# SCH_SCHEMA-LED-3_0_2025-04-29.net
KiCad netlist of a schematic drawn in EasyEDA
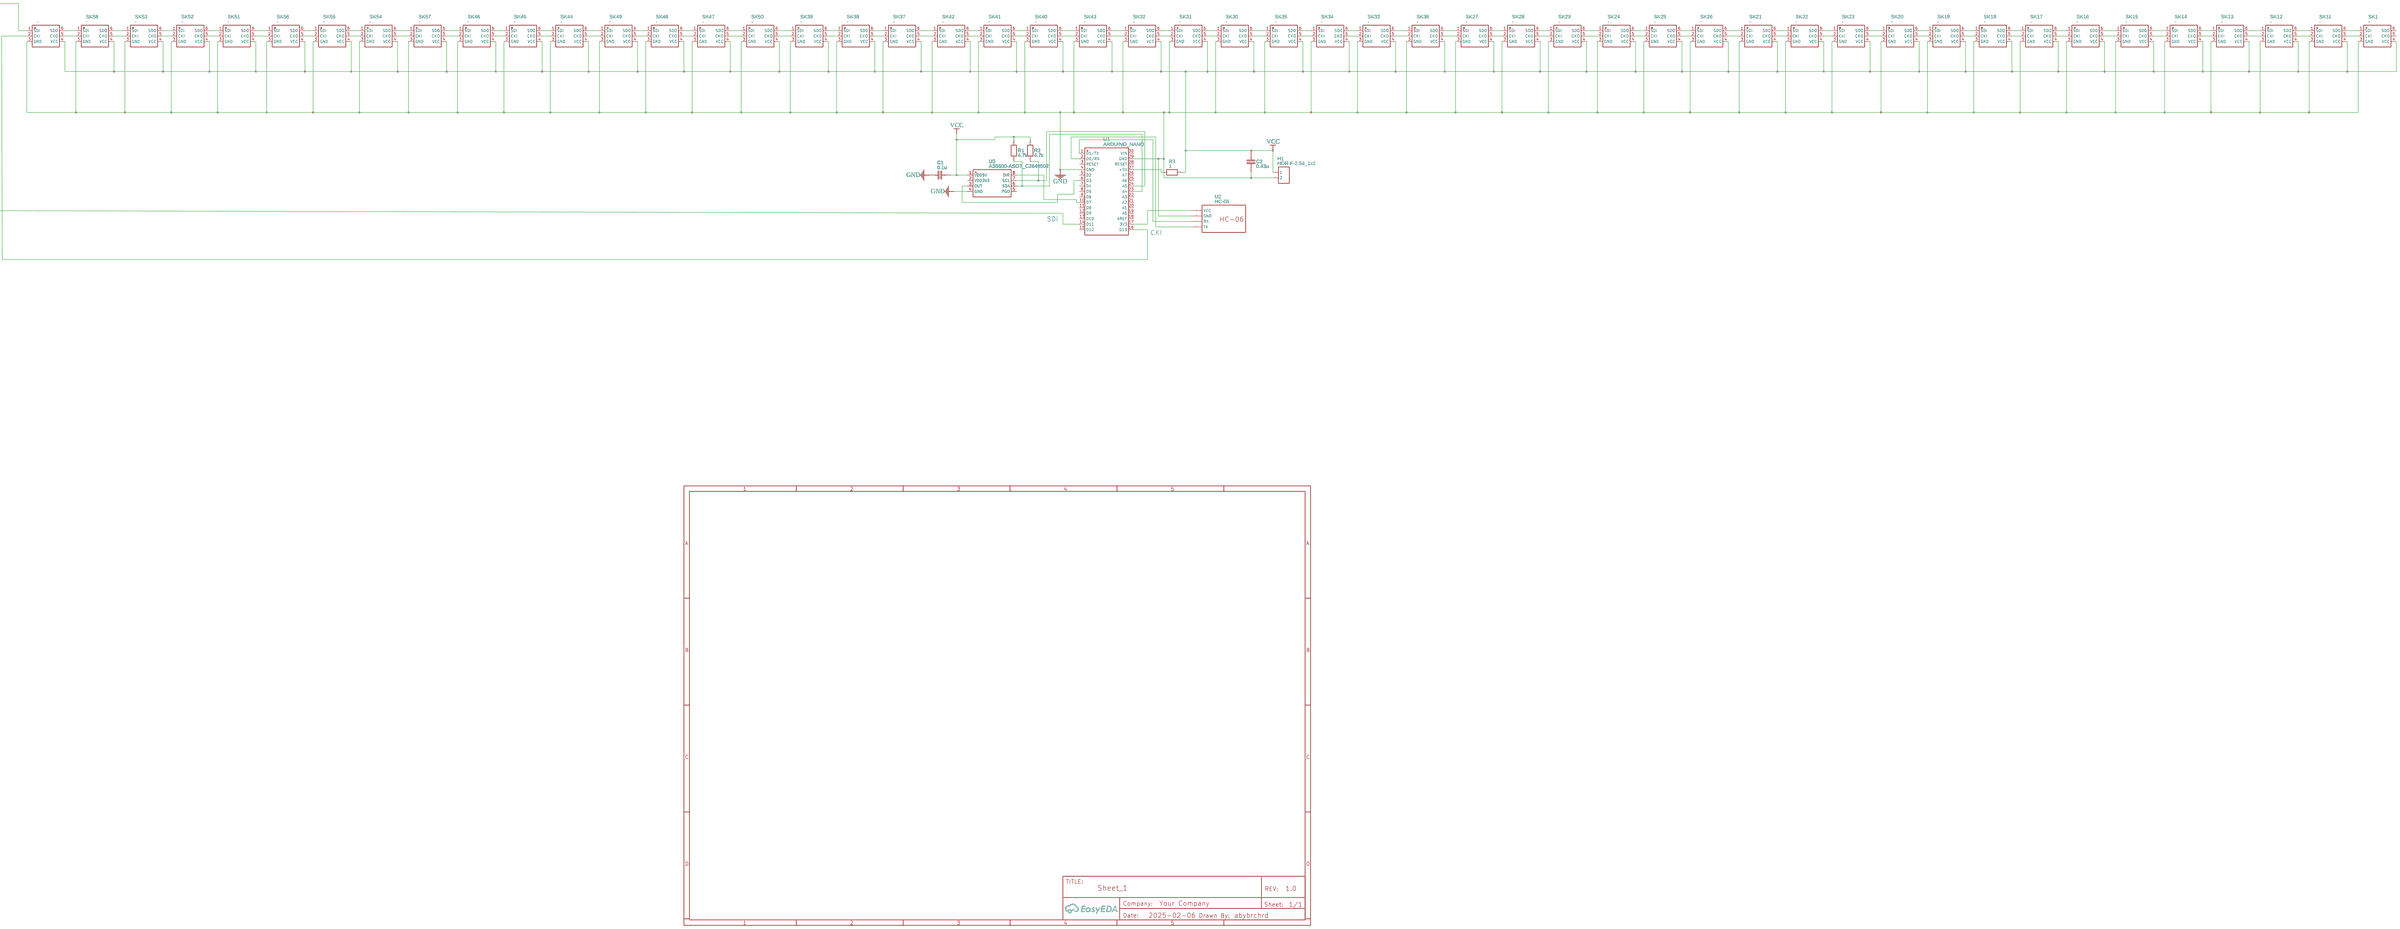
[diagram p0: schematic sheet]

(export (version "E")
  (design (tool "Eeschema 10.0.6"))
  (components
    (comp (ref "C1") (value "0.1u") (libsource (lib "") (part "C_0603_EU")))
    (comp (ref "C2") (value "0.43u") (libsource (lib "") (part "C_1206_EU")))
    (comp (ref "H1") (value "HDR-F-2.54_1x2") (libsource (lib "") (part "HDR-F-2.54_1x2")))
    (comp (ref "R1") (value "4.7k") (libsource (lib "") (part "R_0603_EU")))
    (comp (ref "R2") (value "4.7k") (libsource (lib "") (part "R_0603_EU")))
    (comp (ref "R3") (value "1") (libsource (lib "") (part "R_0603_EU_1")))
    (comp (ref "SK1")
      (value "-")
      (fields (field (name "Manufacturer Part") "SK9822") (field (name "Manufacturer") "欧思科光电"))
      (libsource (lib "") (part "SK9822"))
    )
    (comp (ref "SK11")
      (value "-")
      (fields (field (name "Manufacturer Part") "SK9822") (field (name "Manufacturer") "欧思科光电"))
      (libsource (lib "") (part "SK9822"))
    )
    (comp (ref "SK12")
      (value "-")
      (fields (field (name "Manufacturer Part") "SK9822") (field (name "Manufacturer") "欧思科光电"))
      (libsource (lib "") (part "SK9822"))
    )
    (comp (ref "SK13")
      (value "-")
      (fields (field (name "Manufacturer Part") "SK9822") (field (name "Manufacturer") "欧思科光电"))
      (libsource (lib "") (part "SK9822"))
    )
    (comp (ref "SK14")
      (value "-")
      (fields (field (name "Manufacturer Part") "SK9822") (field (name "Manufacturer") "欧思科光电"))
      (libsource (lib "") (part "SK9822"))
    )
    (comp (ref "SK15")
      (value "-")
      (fields (field (name "Manufacturer Part") "SK9822") (field (name "Manufacturer") "欧思科光电"))
      (libsource (lib "") (part "SK9822"))
    )
    (comp (ref "SK16")
      (value "-")
      (fields (field (name "Manufacturer Part") "SK9822") (field (name "Manufacturer") "欧思科光电"))
      (libsource (lib "") (part "SK9822"))
    )
    (comp (ref "SK17")
      (value "-")
      (fields (field (name "Manufacturer Part") "SK9822") (field (name "Manufacturer") "欧思科光电"))
      (libsource (lib "") (part "SK9822"))
    )
    (comp (ref "SK18")
      (value "-")
      (fields (field (name "Manufacturer Part") "SK9822") (field (name "Manufacturer") "欧思科光电"))
      (libsource (lib "") (part "SK9822"))
    )
    (comp (ref "SK19")
      (value "-")
      (fields (field (name "Manufacturer Part") "SK9822") (field (name "Manufacturer") "欧思科光电"))
      (libsource (lib "") (part "SK9822"))
    )
    (comp (ref "SK20")
      (value "-")
      (fields (field (name "Manufacturer Part") "SK9822") (field (name "Manufacturer") "欧思科光电"))
      (libsource (lib "") (part "SK9822"))
    )
    (comp (ref "SK21")
      (value "-")
      (fields (field (name "Manufacturer Part") "SK9822") (field (name "Manufacturer") "欧思科光电"))
      (libsource (lib "") (part "SK9822"))
    )
    (comp (ref "SK22")
      (value "-")
      (fields (field (name "Manufacturer Part") "SK9822") (field (name "Manufacturer") "欧思科光电"))
      (libsource (lib "") (part "SK9822"))
    )
    (comp (ref "SK23")
      (value "-")
      (fields (field (name "Manufacturer Part") "SK9822") (field (name "Manufacturer") "欧思科光电"))
      (libsource (lib "") (part "SK9822"))
    )
    (comp (ref "SK24")
      (value "-")
      (fields (field (name "Manufacturer Part") "SK9822") (field (name "Manufacturer") "欧思科光电"))
      (libsource (lib "") (part "SK9822"))
    )
    (comp (ref "SK25")
      (value "-")
      (fields (field (name "Manufacturer Part") "SK9822") (field (name "Manufacturer") "欧思科光电"))
      (libsource (lib "") (part "SK9822"))
    )
    (comp (ref "SK26")
      (value "-")
      (fields (field (name "Manufacturer Part") "SK9822") (field (name "Manufacturer") "欧思科光电"))
      (libsource (lib "") (part "SK9822"))
    )
    (comp (ref "SK27")
      (value "-")
      (fields (field (name "Manufacturer Part") "SK9822") (field (name "Manufacturer") "欧思科光电"))
      (libsource (lib "") (part "SK9822"))
    )
    (comp (ref "SK28")
      (value "-")
      (fields (field (name "Manufacturer Part") "SK9822") (field (name "Manufacturer") "欧思科光电"))
      (libsource (lib "") (part "SK9822"))
    )
    (comp (ref "SK29")
      (value "-")
      (fields (field (name "Manufacturer Part") "SK9822") (field (name "Manufacturer") "欧思科光电"))
      (libsource (lib "") (part "SK9822"))
    )
    (comp (ref "SK30")
      (value "-")
      (fields (field (name "Manufacturer Part") "SK9822") (field (name "Manufacturer") "欧思科光电"))
      (libsource (lib "") (part "SK9822"))
    )
    (comp (ref "SK31")
      (value "-")
      (fields (field (name "Manufacturer Part") "SK9822") (field (name "Manufacturer") "欧思科光电"))
      (libsource (lib "") (part "SK9822"))
    )
    (comp (ref "SK32")
      (value "-")
      (fields (field (name "Manufacturer Part") "SK9822") (field (name "Manufacturer") "欧思科光电"))
      (libsource (lib "") (part "SK9822"))
    )
    (comp (ref "SK33")
      (value "-")
      (fields (field (name "Manufacturer Part") "SK9822") (field (name "Manufacturer") "欧思科光电"))
      (libsource (lib "") (part "SK9822"))
    )
    (comp (ref "SK34")
      (value "-")
      (fields (field (name "Manufacturer Part") "SK9822") (field (name "Manufacturer") "欧思科光电"))
      (libsource (lib "") (part "SK9822"))
    )
    (comp (ref "SK35")
      (value "-")
      (fields (field (name "Manufacturer Part") "SK9822") (field (name "Manufacturer") "欧思科光电"))
      (libsource (lib "") (part "SK9822"))
    )
    (comp (ref "SK36")
      (value "-")
      (fields (field (name "Manufacturer Part") "SK9822") (field (name "Manufacturer") "欧思科光电"))
      (libsource (lib "") (part "SK9822"))
    )
    (comp (ref "SK37")
      (value "-")
      (fields (field (name "Manufacturer Part") "SK9822") (field (name "Manufacturer") "欧思科光电"))
      (libsource (lib "") (part "SK9822"))
    )
    (comp (ref "SK38")
      (value "-")
      (fields (field (name "Manufacturer Part") "SK9822") (field (name "Manufacturer") "欧思科光电"))
      (libsource (lib "") (part "SK9822"))
    )
    (comp (ref "SK39")
      (value "-")
      (fields (field (name "Manufacturer Part") "SK9822") (field (name "Manufacturer") "欧思科光电"))
      (libsource (lib "") (part "SK9822"))
    )
    (comp (ref "SK40")
      (value "-")
      (fields (field (name "Manufacturer Part") "SK9822") (field (name "Manufacturer") "欧思科光电"))
      (libsource (lib "") (part "SK9822"))
    )
    (comp (ref "SK41")
      (value "-")
      (fields (field (name "Manufacturer Part") "SK9822") (field (name "Manufacturer") "欧思科光电"))
      (libsource (lib "") (part "SK9822"))
    )
    (comp (ref "SK42")
      (value "-")
      (fields (field (name "Manufacturer Part") "SK9822") (field (name "Manufacturer") "欧思科光电"))
      (libsource (lib "") (part "SK9822"))
    )
    (comp (ref "SK43")
      (value "-")
      (fields (field (name "Manufacturer Part") "SK9822") (field (name "Manufacturer") "欧思科光电"))
      (libsource (lib "") (part "SK9822"))
    )
    (comp (ref "SK44")
      (value "-")
      (fields (field (name "Manufacturer Part") "SK9822") (field (name "Manufacturer") "欧思科光电"))
      (libsource (lib "") (part "SK9822"))
    )
    (comp (ref "SK45")
      (value "-")
      (fields (field (name "Manufacturer Part") "SK9822") (field (name "Manufacturer") "欧思科光电"))
      (libsource (lib "") (part "SK9822"))
    )
    (comp (ref "SK46")
      (value "-")
      (fields (field (name "Manufacturer Part") "SK9822") (field (name "Manufacturer") "欧思科光电"))
      (libsource (lib "") (part "SK9822"))
    )
    (comp (ref "SK47")
      (value "-")
      (fields (field (name "Manufacturer Part") "SK9822") (field (name "Manufacturer") "欧思科光电"))
      (libsource (lib "") (part "SK9822"))
    )
    (comp (ref "SK48")
      (value "-")
      (fields (field (name "Manufacturer Part") "SK9822") (field (name "Manufacturer") "欧思科光电"))
      (libsource (lib "") (part "SK9822"))
    )
    (comp (ref "SK49")
      (value "-")
      (fields (field (name "Manufacturer Part") "SK9822") (field (name "Manufacturer") "欧思科光电"))
      (libsource (lib "") (part "SK9822"))
    )
    (comp (ref "SK50")
      (value "-")
      (fields (field (name "Manufacturer Part") "SK9822") (field (name "Manufacturer") "欧思科光电"))
      (libsource (lib "") (part "SK9822"))
    )
    (comp (ref "SK51")
      (value "-")
      (fields (field (name "Manufacturer Part") "SK9822") (field (name "Manufacturer") "欧思科光电"))
      (libsource (lib "") (part "SK9822"))
    )
    (comp (ref "SK52")
      (value "-")
      (fields (field (name "Manufacturer Part") "SK9822") (field (name "Manufacturer") "欧思科光电"))
      (libsource (lib "") (part "SK9822"))
    )
    (comp (ref "SK53")
      (value "-")
      (fields (field (name "Manufacturer Part") "SK9822") (field (name "Manufacturer") "欧思科光电"))
      (libsource (lib "") (part "SK9822"))
    )
    (comp (ref "SK54")
      (value "-")
      (fields (field (name "Manufacturer Part") "SK9822") (field (name "Manufacturer") "欧思科光电"))
      (libsource (lib "") (part "SK9822"))
    )
    (comp (ref "SK55")
      (value "-")
      (fields (field (name "Manufacturer Part") "SK9822") (field (name "Manufacturer") "欧思科光电"))
      (libsource (lib "") (part "SK9822"))
    )
    (comp (ref "SK56")
      (value "-")
      (fields (field (name "Manufacturer Part") "SK9822") (field (name "Manufacturer") "欧思科光电"))
      (libsource (lib "") (part "SK9822"))
    )
    (comp (ref "SK57")
      (value "-")
      (fields (field (name "Manufacturer Part") "SK9822") (field (name "Manufacturer") "欧思科光电"))
      (libsource (lib "") (part "SK9822"))
    )
    (comp (ref "SK58")
      (value "-")
      (fields (field (name "Manufacturer Part") "SK9822") (field (name "Manufacturer") "欧思科光电"))
      (libsource (lib "") (part "SK9822"))
    )
    (comp (ref "SK59")
      (value "-")
      (fields (field (name "Manufacturer Part") "SK9822") (field (name "Manufacturer") "欧思科光电"))
      (libsource (lib "") (part "SK9822"))
    )
    (comp (ref "U1") (value "ARDUINO_NANO") (libsource (lib "") (part "ARDUINO_NANO")))
    (comp (ref "U2") (value "HC-06") (libsource (lib "") (part "HC-06")))
    (comp (ref "U3")
      (value "AS5600-ASOT_C2649502")
      (fields (field (name "Manufacturer Part") "AS5600-ASOT") (field (name "Manufacturer") "ams(艾迈斯半导体)"))
      (libsource (lib "") (part "AS5600-ASOT_C2649502"))
    )
  )
  (nets
    (net (code "1") (name "GND") (class "Default")
      (node (ref "C1") (pin "1") (pinfunction "1_1") (pintype "unspecified"))
      (node (ref "C2") (pin "1") (pinfunction "1_1") (pintype "unspecified"))
      (node (ref "H1") (pin "2") (pinfunction "2_2") (pintype "input"))
      (node (ref "SK1") (pin "3") (pinfunction "GND_3") (pintype "unspecified"))
      (node (ref "SK11") (pin "3") (pinfunction "GND_3") (pintype "unspecified"))
      (node (ref "SK12") (pin "3") (pinfunction "GND_3") (pintype "unspecified"))
      (node (ref "SK13") (pin "3") (pinfunction "GND_3") (pintype "unspecified"))
      (node (ref "SK14") (pin "3") (pinfunction "GND_3") (pintype "unspecified"))
      (node (ref "SK15") (pin "3") (pinfunction "GND_3") (pintype "unspecified"))
      (node (ref "SK16") (pin "3") (pinfunction "GND_3") (pintype "unspecified"))
      (node (ref "SK17") (pin "3") (pinfunction "GND_3") (pintype "unspecified"))
      (node (ref "SK18") (pin "3") (pinfunction "GND_3") (pintype "unspecified"))
      (node (ref "SK19") (pin "3") (pinfunction "GND_3") (pintype "unspecified"))
      (node (ref "SK20") (pin "3") (pinfunction "GND_3") (pintype "unspecified"))
      (node (ref "SK21") (pin "3") (pinfunction "GND_3") (pintype "unspecified"))
      (node (ref "SK22") (pin "3") (pinfunction "GND_3") (pintype "unspecified"))
      (node (ref "SK23") (pin "3") (pinfunction "GND_3") (pintype "unspecified"))
      (node (ref "SK24") (pin "3") (pinfunction "GND_3") (pintype "unspecified"))
      (node (ref "SK25") (pin "3") (pinfunction "GND_3") (pintype "unspecified"))
      (node (ref "SK26") (pin "3") (pinfunction "GND_3") (pintype "unspecified"))
      (node (ref "SK27") (pin "3") (pinfunction "GND_3") (pintype "unspecified"))
      (node (ref "SK28") (pin "3") (pinfunction "GND_3") (pintype "unspecified"))
      (node (ref "SK29") (pin "3") (pinfunction "GND_3") (pintype "unspecified"))
      (node (ref "SK30") (pin "3") (pinfunction "GND_3") (pintype "unspecified"))
      (node (ref "SK31") (pin "3") (pinfunction "GND_3") (pintype "unspecified"))
      (node (ref "SK32") (pin "3") (pinfunction "GND_3") (pintype "unspecified"))
      (node (ref "SK33") (pin "3") (pinfunction "GND_3") (pintype "unspecified"))
      (node (ref "SK34") (pin "3") (pinfunction "GND_3") (pintype "unspecified"))
      (node (ref "SK35") (pin "3") (pinfunction "GND_3") (pintype "unspecified"))
      (node (ref "SK36") (pin "3") (pinfunction "GND_3") (pintype "unspecified"))
      (node (ref "SK37") (pin "3") (pinfunction "GND_3") (pintype "unspecified"))
      (node (ref "SK38") (pin "3") (pinfunction "GND_3") (pintype "unspecified"))
      (node (ref "SK39") (pin "3") (pinfunction "GND_3") (pintype "unspecified"))
      (node (ref "SK40") (pin "3") (pinfunction "GND_3") (pintype "unspecified"))
      (node (ref "SK41") (pin "3") (pinfunction "GND_3") (pintype "unspecified"))
      (node (ref "SK42") (pin "3") (pinfunction "GND_3") (pintype "unspecified"))
      (node (ref "SK43") (pin "3") (pinfunction "GND_3") (pintype "unspecified"))
      (node (ref "SK44") (pin "3") (pinfunction "GND_3") (pintype "unspecified"))
      (node (ref "SK45") (pin "3") (pinfunction "GND_3") (pintype "unspecified"))
      (node (ref "SK46") (pin "3") (pinfunction "GND_3") (pintype "unspecified"))
      (node (ref "SK47") (pin "3") (pinfunction "GND_3") (pintype "unspecified"))
      (node (ref "SK48") (pin "3") (pinfunction "GND_3") (pintype "unspecified"))
      (node (ref "SK49") (pin "3") (pinfunction "GND_3") (pintype "unspecified"))
      (node (ref "SK50") (pin "3") (pinfunction "GND_3") (pintype "unspecified"))
      (node (ref "SK51") (pin "3") (pinfunction "GND_3") (pintype "unspecified"))
      (node (ref "SK52") (pin "3") (pinfunction "GND_3") (pintype "unspecified"))
      (node (ref "SK53") (pin "3") (pinfunction "GND_3") (pintype "unspecified"))
      (node (ref "SK54") (pin "3") (pinfunction "GND_3") (pintype "unspecified"))
      (node (ref "SK55") (pin "3") (pinfunction "GND_3") (pintype "unspecified"))
      (node (ref "SK56") (pin "3") (pinfunction "GND_3") (pintype "unspecified"))
      (node (ref "SK57") (pin "3") (pinfunction "GND_3") (pintype "unspecified"))
      (node (ref "SK58") (pin "3") (pinfunction "GND_3") (pintype "unspecified"))
      (node (ref "SK59") (pin "3") (pinfunction "GND_3") (pintype "unspecified"))
      (node (ref "U1") (pin "29") (pinfunction "GND_29") (pintype "unspecified"))
      (node (ref "U1") (pin "4") (pinfunction "GND_4") (pintype "unspecified"))
      (node (ref "U2") (pin "3") (pinfunction "GND_3") (pintype "unspecified"))
      (node (ref "U3") (pin "4") (pinfunction "GND_4") (pintype "unspecified"))
    )
    (net (code "2") (name "Net-(SK1-CKI)") (class "Default")
      (node (ref "SK1") (pin "2") (pinfunction "CKI_2") (pintype "unspecified"))
      (node (ref "SK11") (pin "5") (pinfunction "CKO_5") (pintype "unspecified"))
    )
    (net (code "3") (name "Net-(SK1-SDI)") (class "Default")
      (node (ref "SK1") (pin "1") (pinfunction "SDI_1") (pintype "unspecified"))
      (node (ref "SK11") (pin "6") (pinfunction "SDO_6") (pintype "unspecified"))
    )
    (net (code "4") (name "Net-(SK11-CKI)") (class "Default")
      (node (ref "SK11") (pin "2") (pinfunction "CKI_2") (pintype "unspecified"))
      (node (ref "SK12") (pin "5") (pinfunction "CKO_5") (pintype "unspecified"))
    )
    (net (code "5") (name "Net-(SK11-SDI)") (class "Default")
      (node (ref "SK11") (pin "1") (pinfunction "SDI_1") (pintype "unspecified"))
      (node (ref "SK12") (pin "6") (pinfunction "SDO_6") (pintype "unspecified"))
    )
    (net (code "6") (name "Net-(SK12-CKI)") (class "Default")
      (node (ref "SK12") (pin "2") (pinfunction "CKI_2") (pintype "unspecified"))
      (node (ref "SK13") (pin "5") (pinfunction "CKO_5") (pintype "unspecified"))
    )
    (net (code "7") (name "Net-(SK12-SDI)") (class "Default")
      (node (ref "SK12") (pin "1") (pinfunction "SDI_1") (pintype "unspecified"))
      (node (ref "SK13") (pin "6") (pinfunction "SDO_6") (pintype "unspecified"))
    )
    (net (code "8") (name "Net-(SK13-CKI)") (class "Default")
      (node (ref "SK13") (pin "2") (pinfunction "CKI_2") (pintype "unspecified"))
      (node (ref "SK14") (pin "5") (pinfunction "CKO_5") (pintype "unspecified"))
    )
    (net (code "9") (name "Net-(SK13-SDI)") (class "Default")
      (node (ref "SK13") (pin "1") (pinfunction "SDI_1") (pintype "unspecified"))
      (node (ref "SK14") (pin "6") (pinfunction "SDO_6") (pintype "unspecified"))
    )
    (net (code "10") (name "Net-(SK14-CKI)") (class "Default")
      (node (ref "SK14") (pin "2") (pinfunction "CKI_2") (pintype "unspecified"))
      (node (ref "SK15") (pin "5") (pinfunction "CKO_5") (pintype "unspecified"))
    )
    (net (code "11") (name "Net-(SK14-SDI)") (class "Default")
      (node (ref "SK14") (pin "1") (pinfunction "SDI_1") (pintype "unspecified"))
      (node (ref "SK15") (pin "6") (pinfunction "SDO_6") (pintype "unspecified"))
    )
    (net (code "12") (name "Net-(SK15-CKI)") (class "Default")
      (node (ref "SK15") (pin "2") (pinfunction "CKI_2") (pintype "unspecified"))
      (node (ref "SK16") (pin "5") (pinfunction "CKO_5") (pintype "unspecified"))
    )
    (net (code "13") (name "Net-(SK15-SDI)") (class "Default")
      (node (ref "SK15") (pin "1") (pinfunction "SDI_1") (pintype "unspecified"))
      (node (ref "SK16") (pin "6") (pinfunction "SDO_6") (pintype "unspecified"))
    )
    (net (code "14") (name "Net-(SK16-CKI)") (class "Default")
      (node (ref "SK16") (pin "2") (pinfunction "CKI_2") (pintype "unspecified"))
      (node (ref "SK17") (pin "5") (pinfunction "CKO_5") (pintype "unspecified"))
    )
    (net (code "15") (name "Net-(SK16-SDI)") (class "Default")
      (node (ref "SK16") (pin "1") (pinfunction "SDI_1") (pintype "unspecified"))
      (node (ref "SK17") (pin "6") (pinfunction "SDO_6") (pintype "unspecified"))
    )
    (net (code "16") (name "Net-(SK17-CKI)") (class "Default")
      (node (ref "SK17") (pin "2") (pinfunction "CKI_2") (pintype "unspecified"))
      (node (ref "SK18") (pin "5") (pinfunction "CKO_5") (pintype "unspecified"))
    )
    (net (code "17") (name "Net-(SK17-SDI)") (class "Default")
      (node (ref "SK17") (pin "1") (pinfunction "SDI_1") (pintype "unspecified"))
      (node (ref "SK18") (pin "6") (pinfunction "SDO_6") (pintype "unspecified"))
    )
    (net (code "18") (name "Net-(SK18-CKI)") (class "Default")
      (node (ref "SK18") (pin "2") (pinfunction "CKI_2") (pintype "unspecified"))
      (node (ref "SK19") (pin "5") (pinfunction "CKO_5") (pintype "unspecified"))
    )
    (net (code "19") (name "Net-(SK18-SDI)") (class "Default")
      (node (ref "SK18") (pin "1") (pinfunction "SDI_1") (pintype "unspecified"))
      (node (ref "SK19") (pin "6") (pinfunction "SDO_6") (pintype "unspecified"))
    )
    (net (code "20") (name "Net-(SK19-CKI)") (class "Default")
      (node (ref "SK19") (pin "2") (pinfunction "CKI_2") (pintype "unspecified"))
      (node (ref "SK20") (pin "5") (pinfunction "CKO_5") (pintype "unspecified"))
    )
    (net (code "21") (name "Net-(SK19-SDI)") (class "Default")
      (node (ref "SK19") (pin "1") (pinfunction "SDI_1") (pintype "unspecified"))
      (node (ref "SK20") (pin "6") (pinfunction "SDO_6") (pintype "unspecified"))
    )
    (net (code "22") (name "Net-(SK20-CKI)") (class "Default")
      (node (ref "SK20") (pin "2") (pinfunction "CKI_2") (pintype "unspecified"))
      (node (ref "SK23") (pin "5") (pinfunction "CKO_5") (pintype "unspecified"))
    )
    (net (code "23") (name "Net-(SK20-SDI)") (class "Default")
      (node (ref "SK20") (pin "1") (pinfunction "SDI_1") (pintype "unspecified"))
      (node (ref "SK23") (pin "6") (pinfunction "SDO_6") (pintype "unspecified"))
    )
    (net (code "24") (name "Net-(SK21-CKI)") (class "Default")
      (node (ref "SK21") (pin "2") (pinfunction "CKI_2") (pintype "unspecified"))
      (node (ref "SK26") (pin "5") (pinfunction "CKO_5") (pintype "unspecified"))
    )
    (net (code "25") (name "Net-(SK21-CKO)") (class "Default")
      (node (ref "SK21") (pin "5") (pinfunction "CKO_5") (pintype "unspecified"))
      (node (ref "SK22") (pin "2") (pinfunction "CKI_2") (pintype "unspecified"))
    )
    (net (code "26") (name "Net-(SK21-SDI)") (class "Default")
      (node (ref "SK21") (pin "1") (pinfunction "SDI_1") (pintype "unspecified"))
      (node (ref "SK26") (pin "6") (pinfunction "SDO_6") (pintype "unspecified"))
    )
    (net (code "27") (name "Net-(SK21-SDO)") (class "Default")
      (node (ref "SK21") (pin "6") (pinfunction "SDO_6") (pintype "unspecified"))
      (node (ref "SK22") (pin "1") (pinfunction "SDI_1") (pintype "unspecified"))
    )
    (net (code "28") (name "Net-(SK22-CKO)") (class "Default")
      (node (ref "SK22") (pin "5") (pinfunction "CKO_5") (pintype "unspecified"))
      (node (ref "SK23") (pin "2") (pinfunction "CKI_2") (pintype "unspecified"))
    )
    (net (code "29") (name "Net-(SK22-SDO)") (class "Default")
      (node (ref "SK22") (pin "6") (pinfunction "SDO_6") (pintype "unspecified"))
      (node (ref "SK23") (pin "1") (pinfunction "SDI_1") (pintype "unspecified"))
    )
    (net (code "30") (name "Net-(SK24-CKI)") (class "Default")
      (node (ref "SK24") (pin "2") (pinfunction "CKI_2") (pintype "unspecified"))
      (node (ref "SK29") (pin "5") (pinfunction "CKO_5") (pintype "unspecified"))
    )
    (net (code "31") (name "Net-(SK24-CKO)") (class "Default")
      (node (ref "SK24") (pin "5") (pinfunction "CKO_5") (pintype "unspecified"))
      (node (ref "SK25") (pin "2") (pinfunction "CKI_2") (pintype "unspecified"))
    )
    (net (code "32") (name "Net-(SK24-SDI)") (class "Default")
      (node (ref "SK24") (pin "1") (pinfunction "SDI_1") (pintype "unspecified"))
      (node (ref "SK29") (pin "6") (pinfunction "SDO_6") (pintype "unspecified"))
    )
    (net (code "33") (name "Net-(SK24-SDO)") (class "Default")
      (node (ref "SK24") (pin "6") (pinfunction "SDO_6") (pintype "unspecified"))
      (node (ref "SK25") (pin "1") (pinfunction "SDI_1") (pintype "unspecified"))
    )
    (net (code "34") (name "Net-(SK25-CKO)") (class "Default")
      (node (ref "SK25") (pin "5") (pinfunction "CKO_5") (pintype "unspecified"))
      (node (ref "SK26") (pin "2") (pinfunction "CKI_2") (pintype "unspecified"))
    )
    (net (code "35") (name "Net-(SK25-SDO)") (class "Default")
      (node (ref "SK25") (pin "6") (pinfunction "SDO_6") (pintype "unspecified"))
      (node (ref "SK26") (pin "1") (pinfunction "SDI_1") (pintype "unspecified"))
    )
    (net (code "36") (name "Net-(SK27-CKI)") (class "Default")
      (node (ref "SK27") (pin "2") (pinfunction "CKI_2") (pintype "unspecified"))
      (node (ref "SK36") (pin "5") (pinfunction "CKO_5") (pintype "unspecified"))
    )
    (net (code "37") (name "Net-(SK27-CKO)") (class "Default")
      (node (ref "SK27") (pin "5") (pinfunction "CKO_5") (pintype "unspecified"))
      (node (ref "SK28") (pin "2") (pinfunction "CKI_2") (pintype "unspecified"))
    )
    (net (code "38") (name "Net-(SK27-SDI)") (class "Default")
      (node (ref "SK27") (pin "1") (pinfunction "SDI_1") (pintype "unspecified"))
      (node (ref "SK36") (pin "6") (pinfunction "SDO_6") (pintype "unspecified"))
    )
    (net (code "39") (name "Net-(SK27-SDO)") (class "Default")
      (node (ref "SK27") (pin "6") (pinfunction "SDO_6") (pintype "unspecified"))
      (node (ref "SK28") (pin "1") (pinfunction "SDI_1") (pintype "unspecified"))
    )
    (net (code "40") (name "Net-(SK28-CKO)") (class "Default")
      (node (ref "SK28") (pin "5") (pinfunction "CKO_5") (pintype "unspecified"))
      (node (ref "SK29") (pin "2") (pinfunction "CKI_2") (pintype "unspecified"))
    )
    (net (code "41") (name "Net-(SK28-SDO)") (class "Default")
      (node (ref "SK28") (pin "6") (pinfunction "SDO_6") (pintype "unspecified"))
      (node (ref "SK29") (pin "1") (pinfunction "SDI_1") (pintype "unspecified"))
    )
    (net (code "42") (name "Net-(SK30-CKI)") (class "Default")
      (node (ref "SK30") (pin "2") (pinfunction "CKI_2") (pintype "unspecified"))
      (node (ref "SK31") (pin "5") (pinfunction "CKO_5") (pintype "unspecified"))
    )
    (net (code "43") (name "Net-(SK30-CKO)") (class "Default")
      (node (ref "SK30") (pin "5") (pinfunction "CKO_5") (pintype "unspecified"))
      (node (ref "SK35") (pin "2") (pinfunction "CKI_2") (pintype "unspecified"))
    )
    (net (code "44") (name "Net-(SK30-SDI)") (class "Default")
      (node (ref "SK30") (pin "1") (pinfunction "SDI_1") (pintype "unspecified"))
      (node (ref "SK31") (pin "6") (pinfunction "SDO_6") (pintype "unspecified"))
    )
    (net (code "45") (name "Net-(SK30-SDO)") (class "Default")
      (node (ref "SK30") (pin "6") (pinfunction "SDO_6") (pintype "unspecified"))
      (node (ref "SK35") (pin "1") (pinfunction "SDI_1") (pintype "unspecified"))
    )
    (net (code "46") (name "Net-(SK31-CKI)") (class "Default")
      (node (ref "SK31") (pin "2") (pinfunction "CKI_2") (pintype "unspecified"))
      (node (ref "SK32") (pin "5") (pinfunction "CKO_5") (pintype "unspecified"))
    )
    (net (code "47") (name "Net-(SK31-SDI)") (class "Default")
      (node (ref "SK31") (pin "1") (pinfunction "SDI_1") (pintype "unspecified"))
      (node (ref "SK32") (pin "6") (pinfunction "SDO_6") (pintype "unspecified"))
    )
    (net (code "48") (name "Net-(SK32-CKI)") (class "Default")
      (node (ref "SK32") (pin "2") (pinfunction "CKI_2") (pintype "unspecified"))
      (node (ref "SK43") (pin "5") (pinfunction "CKO_5") (pintype "unspecified"))
    )
    (net (code "49") (name "Net-(SK32-SDI)") (class "Default")
      (node (ref "SK32") (pin "1") (pinfunction "SDI_1") (pintype "unspecified"))
      (node (ref "SK43") (pin "6") (pinfunction "SDO_6") (pintype "unspecified"))
    )
    (net (code "50") (name "Net-(SK33-CKI)") (class "Default")
      (node (ref "SK33") (pin "2") (pinfunction "CKI_2") (pintype "unspecified"))
      (node (ref "SK34") (pin "5") (pinfunction "CKO_5") (pintype "unspecified"))
    )
    (net (code "51") (name "Net-(SK33-CKO)") (class "Default")
      (node (ref "SK33") (pin "5") (pinfunction "CKO_5") (pintype "unspecified"))
      (node (ref "SK36") (pin "2") (pinfunction "CKI_2") (pintype "unspecified"))
    )
    (net (code "52") (name "Net-(SK33-SDI)") (class "Default")
      (node (ref "SK33") (pin "1") (pinfunction "SDI_1") (pintype "unspecified"))
      (node (ref "SK34") (pin "6") (pinfunction "SDO_6") (pintype "unspecified"))
    )
    (net (code "53") (name "Net-(SK33-SDO)") (class "Default")
      (node (ref "SK33") (pin "6") (pinfunction "SDO_6") (pintype "unspecified"))
      (node (ref "SK36") (pin "1") (pinfunction "SDI_1") (pintype "unspecified"))
    )
    (net (code "54") (name "Net-(SK34-CKI)") (class "Default")
      (node (ref "SK34") (pin "2") (pinfunction "CKI_2") (pintype "unspecified"))
      (node (ref "SK35") (pin "5") (pinfunction "CKO_5") (pintype "unspecified"))
    )
    (net (code "55") (name "Net-(SK34-SDI)") (class "Default")
      (node (ref "SK34") (pin "1") (pinfunction "SDI_1") (pintype "unspecified"))
      (node (ref "SK35") (pin "6") (pinfunction "SDO_6") (pintype "unspecified"))
    )
    (net (code "56") (name "Net-(SK37-CKI)") (class "Default")
      (node (ref "SK37") (pin "2") (pinfunction "CKI_2") (pintype "unspecified"))
      (node (ref "SK38") (pin "5") (pinfunction "CKO_5") (pintype "unspecified"))
    )
    (net (code "57") (name "Net-(SK37-CKO)") (class "Default")
      (node (ref "SK37") (pin "5") (pinfunction "CKO_5") (pintype "unspecified"))
      (node (ref "SK42") (pin "2") (pinfunction "CKI_2") (pintype "unspecified"))
    )
    (net (code "58") (name "Net-(SK37-SDI)") (class "Default")
      (node (ref "SK37") (pin "1") (pinfunction "SDI_1") (pintype "unspecified"))
      (node (ref "SK38") (pin "6") (pinfunction "SDO_6") (pintype "unspecified"))
    )
    (net (code "59") (name "Net-(SK37-SDO)") (class "Default")
      (node (ref "SK37") (pin "6") (pinfunction "SDO_6") (pintype "unspecified"))
      (node (ref "SK42") (pin "1") (pinfunction "SDI_1") (pintype "unspecified"))
    )
    (net (code "60") (name "Net-(SK38-CKI)") (class "Default")
      (node (ref "SK38") (pin "2") (pinfunction "CKI_2") (pintype "unspecified"))
      (node (ref "SK39") (pin "5") (pinfunction "CKO_5") (pintype "unspecified"))
    )
    (net (code "61") (name "Net-(SK38-SDI)") (class "Default")
      (node (ref "SK38") (pin "1") (pinfunction "SDI_1") (pintype "unspecified"))
      (node (ref "SK39") (pin "6") (pinfunction "SDO_6") (pintype "unspecified"))
    )
    (net (code "62") (name "Net-(SK39-CKI)") (class "Default")
      (node (ref "SK39") (pin "2") (pinfunction "CKI_2") (pintype "unspecified"))
      (node (ref "SK50") (pin "5") (pinfunction "CKO_5") (pintype "unspecified"))
    )
    (net (code "63") (name "Net-(SK39-SDI)") (class "Default")
      (node (ref "SK39") (pin "1") (pinfunction "SDI_1") (pintype "unspecified"))
      (node (ref "SK50") (pin "6") (pinfunction "SDO_6") (pintype "unspecified"))
    )
    (net (code "64") (name "Net-(SK40-CKI)") (class "Default")
      (node (ref "SK40") (pin "2") (pinfunction "CKI_2") (pintype "unspecified"))
      (node (ref "SK41") (pin "5") (pinfunction "CKO_5") (pintype "unspecified"))
    )
    (net (code "65") (name "Net-(SK40-CKO)") (class "Default")
      (node (ref "SK40") (pin "5") (pinfunction "CKO_5") (pintype "unspecified"))
      (node (ref "SK43") (pin "2") (pinfunction "CKI_2") (pintype "unspecified"))
    )
    (net (code "66") (name "Net-(SK40-SDI)") (class "Default")
      (node (ref "SK40") (pin "1") (pinfunction "SDI_1") (pintype "unspecified"))
      (node (ref "SK41") (pin "6") (pinfunction "SDO_6") (pintype "unspecified"))
    )
    (net (code "67") (name "Net-(SK40-SDO)") (class "Default")
      (node (ref "SK40") (pin "6") (pinfunction "SDO_6") (pintype "unspecified"))
      (node (ref "SK43") (pin "1") (pinfunction "SDI_1") (pintype "unspecified"))
    )
    (net (code "68") (name "Net-(SK41-CKI)") (class "Default")
      (node (ref "SK41") (pin "2") (pinfunction "CKI_2") (pintype "unspecified"))
      (node (ref "SK42") (pin "5") (pinfunction "CKO_5") (pintype "unspecified"))
    )
    (net (code "69") (name "Net-(SK41-SDI)") (class "Default")
      (node (ref "SK41") (pin "1") (pinfunction "SDI_1") (pintype "unspecified"))
      (node (ref "SK42") (pin "6") (pinfunction "SDO_6") (pintype "unspecified"))
    )
    (net (code "70") (name "Net-(SK44-CKI)") (class "Default")
      (node (ref "SK44") (pin "2") (pinfunction "CKI_2") (pintype "unspecified"))
      (node (ref "SK45") (pin "5") (pinfunction "CKO_5") (pintype "unspecified"))
    )
    (net (code "71") (name "Net-(SK44-CKO)") (class "Default")
      (node (ref "SK44") (pin "5") (pinfunction "CKO_5") (pintype "unspecified"))
      (node (ref "SK49") (pin "2") (pinfunction "CKI_2") (pintype "unspecified"))
    )
    (net (code "72") (name "Net-(SK44-SDI)") (class "Default")
      (node (ref "SK44") (pin "1") (pinfunction "SDI_1") (pintype "unspecified"))
      (node (ref "SK45") (pin "6") (pinfunction "SDO_6") (pintype "unspecified"))
    )
    (net (code "73") (name "Net-(SK44-SDO)") (class "Default")
      (node (ref "SK44") (pin "6") (pinfunction "SDO_6") (pintype "unspecified"))
      (node (ref "SK49") (pin "1") (pinfunction "SDI_1") (pintype "unspecified"))
    )
    (net (code "74") (name "Net-(SK45-CKI)") (class "Default")
      (node (ref "SK45") (pin "2") (pinfunction "CKI_2") (pintype "unspecified"))
      (node (ref "SK46") (pin "5") (pinfunction "CKO_5") (pintype "unspecified"))
    )
    (net (code "75") (name "Net-(SK45-SDI)") (class "Default")
      (node (ref "SK45") (pin "1") (pinfunction "SDI_1") (pintype "unspecified"))
      (node (ref "SK46") (pin "6") (pinfunction "SDO_6") (pintype "unspecified"))
    )
    (net (code "76") (name "Net-(SK46-CKI)") (class "Default")
      (node (ref "SK46") (pin "2") (pinfunction "CKI_2") (pintype "unspecified"))
      (node (ref "SK57") (pin "5") (pinfunction "CKO_5") (pintype "unspecified"))
    )
    (net (code "77") (name "Net-(SK46-SDI)") (class "Default")
      (node (ref "SK46") (pin "1") (pinfunction "SDI_1") (pintype "unspecified"))
      (node (ref "SK57") (pin "6") (pinfunction "SDO_6") (pintype "unspecified"))
    )
    (net (code "78") (name "Net-(SK47-CKI)") (class "Default")
      (node (ref "SK47") (pin "2") (pinfunction "CKI_2") (pintype "unspecified"))
      (node (ref "SK48") (pin "5") (pinfunction "CKO_5") (pintype "unspecified"))
    )
    (net (code "79") (name "Net-(SK47-CKO)") (class "Default")
      (node (ref "SK47") (pin "5") (pinfunction "CKO_5") (pintype "unspecified"))
      (node (ref "SK50") (pin "2") (pinfunction "CKI_2") (pintype "unspecified"))
    )
    (net (code "80") (name "Net-(SK47-SDI)") (class "Default")
      (node (ref "SK47") (pin "1") (pinfunction "SDI_1") (pintype "unspecified"))
      (node (ref "SK48") (pin "6") (pinfunction "SDO_6") (pintype "unspecified"))
    )
    (net (code "81") (name "Net-(SK47-SDO)") (class "Default")
      (node (ref "SK47") (pin "6") (pinfunction "SDO_6") (pintype "unspecified"))
      (node (ref "SK50") (pin "1") (pinfunction "SDI_1") (pintype "unspecified"))
    )
    (net (code "82") (name "Net-(SK48-CKI)") (class "Default")
      (node (ref "SK48") (pin "2") (pinfunction "CKI_2") (pintype "unspecified"))
      (node (ref "SK49") (pin "5") (pinfunction "CKO_5") (pintype "unspecified"))
    )
    (net (code "83") (name "Net-(SK48-SDI)") (class "Default")
      (node (ref "SK48") (pin "1") (pinfunction "SDI_1") (pintype "unspecified"))
      (node (ref "SK49") (pin "6") (pinfunction "SDO_6") (pintype "unspecified"))
    )
    (net (code "84") (name "Net-(SK51-CKI)") (class "Default")
      (node (ref "SK51") (pin "2") (pinfunction "CKI_2") (pintype "unspecified"))
      (node (ref "SK52") (pin "5") (pinfunction "CKO_5") (pintype "unspecified"))
    )
    (net (code "85") (name "Net-(SK51-CKO)") (class "Default")
      (node (ref "SK51") (pin "5") (pinfunction "CKO_5") (pintype "unspecified"))
      (node (ref "SK56") (pin "2") (pinfunction "CKI_2") (pintype "unspecified"))
    )
    (net (code "86") (name "Net-(SK51-SDI)") (class "Default")
      (node (ref "SK51") (pin "1") (pinfunction "SDI_1") (pintype "unspecified"))
      (node (ref "SK52") (pin "6") (pinfunction "SDO_6") (pintype "unspecified"))
    )
    (net (code "87") (name "Net-(SK51-SDO)") (class "Default")
      (node (ref "SK51") (pin "6") (pinfunction "SDO_6") (pintype "unspecified"))
      (node (ref "SK56") (pin "1") (pinfunction "SDI_1") (pintype "unspecified"))
    )
    (net (code "88") (name "Net-(SK52-CKI)") (class "Default")
      (node (ref "SK52") (pin "2") (pinfunction "CKI_2") (pintype "unspecified"))
      (node (ref "SK53") (pin "5") (pinfunction "CKO_5") (pintype "unspecified"))
    )
    (net (code "89") (name "Net-(SK52-SDI)") (class "Default")
      (node (ref "SK52") (pin "1") (pinfunction "SDI_1") (pintype "unspecified"))
      (node (ref "SK53") (pin "6") (pinfunction "SDO_6") (pintype "unspecified"))
    )
    (net (code "90") (name "Net-(SK53-CKI)") (class "Default")
      (node (ref "SK53") (pin "2") (pinfunction "CKI_2") (pintype "unspecified"))
      (node (ref "SK58") (pin "5") (pinfunction "CKO_5") (pintype "unspecified"))
    )
    (net (code "91") (name "Net-(SK53-SDI)") (class "Default")
      (node (ref "SK53") (pin "1") (pinfunction "SDI_1") (pintype "unspecified"))
      (node (ref "SK58") (pin "6") (pinfunction "SDO_6") (pintype "unspecified"))
    )
    (net (code "92") (name "Net-(SK54-CKI)") (class "Default")
      (node (ref "SK54") (pin "2") (pinfunction "CKI_2") (pintype "unspecified"))
      (node (ref "SK55") (pin "5") (pinfunction "CKO_5") (pintype "unspecified"))
    )
    (net (code "93") (name "Net-(SK54-CKO)") (class "Default")
      (node (ref "SK54") (pin "5") (pinfunction "CKO_5") (pintype "unspecified"))
      (node (ref "SK57") (pin "2") (pinfunction "CKI_2") (pintype "unspecified"))
    )
    (net (code "94") (name "Net-(SK54-SDI)") (class "Default")
      (node (ref "SK54") (pin "1") (pinfunction "SDI_1") (pintype "unspecified"))
      (node (ref "SK55") (pin "6") (pinfunction "SDO_6") (pintype "unspecified"))
    )
    (net (code "95") (name "Net-(SK54-SDO)") (class "Default")
      (node (ref "SK54") (pin "6") (pinfunction "SDO_6") (pintype "unspecified"))
      (node (ref "SK57") (pin "1") (pinfunction "SDI_1") (pintype "unspecified"))
    )
    (net (code "96") (name "Net-(SK55-CKI)") (class "Default")
      (node (ref "SK55") (pin "2") (pinfunction "CKI_2") (pintype "unspecified"))
      (node (ref "SK56") (pin "5") (pinfunction "CKO_5") (pintype "unspecified"))
    )
    (net (code "97") (name "Net-(SK55-SDI)") (class "Default")
      (node (ref "SK55") (pin "1") (pinfunction "SDI_1") (pintype "unspecified"))
      (node (ref "SK56") (pin "6") (pinfunction "SDO_6") (pintype "unspecified"))
    )
    (net (code "98") (name "Net-(SK58-CKI)") (class "Default")
      (node (ref "SK58") (pin "2") (pinfunction "CKI_2") (pintype "unspecified"))
      (node (ref "SK59") (pin "5") (pinfunction "CKO_5") (pintype "unspecified"))
    )
    (net (code "99") (name "Net-(SK58-SDI)") (class "Default")
      (node (ref "SK58") (pin "1") (pinfunction "SDI_1") (pintype "unspecified"))
      (node (ref "SK59") (pin "6") (pinfunction "SDO_6") (pintype "unspecified"))
    )
    (net (code "100") (name "Net-(SK59-CKI)") (class "Default")
      (node (ref "SK59") (pin "2") (pinfunction "CKI_2") (pintype "unspecified"))
      (node (ref "U1") (pin "16") (pinfunction "D13_16") (pintype "unspecified"))
    )
    (net (code "101") (name "Net-(SK59-SDI)") (class "Default")
      (node (ref "SK59") (pin "1") (pinfunction "SDI_1") (pintype "unspecified"))
      (node (ref "U1") (pin "14") (pinfunction "D11_14") (pintype "unspecified"))
    )
    (net (code "102") (name "Net-(U1-+5V)") (class "Default")
      (node (ref "R3") (pin "1") (pinfunction "1_1") (pintype "unspecified"))
      (node (ref "U1") (pin "27") (pinfunction "+5V_27") (pintype "unspecified"))
    )
    (net (code "103") (name "Net-(U1-3V3)") (class "Default")
      (node (ref "U1") (pin "17") (pinfunction "3V3_17") (pintype "unspecified"))
      (node (ref "U2") (pin "4") (pinfunction "VCC_4") (pintype "unspecified"))
    )
    (net (code "104") (name "Net-(U1-A4)") (class "Default")
      (node (ref "R1") (pin "1") (pinfunction "1_1") (pintype "unspecified"))
      (node (ref "U1") (pin "23") (pinfunction "A4_23") (pintype "unspecified"))
      (node (ref "U3") (pin "6") (pinfunction "SDA_6") (pintype "unspecified"))
    )
    (net (code "105") (name "Net-(U1-A5)") (class "Default")
      (node (ref "R2") (pin "1") (pinfunction "1_1") (pintype "unspecified"))
      (node (ref "U1") (pin "24") (pinfunction "A5_24") (pintype "unspecified"))
      (node (ref "U3") (pin "7") (pinfunction "SCL_7") (pintype "unspecified"))
    )
    (net (code "106") (name "Net-(U1-D0{slash}RX)") (class "Default")
      (node (ref "U1") (pin "2") (pinfunction "D0/RX_2") (pintype "unspecified"))
      (node (ref "U2") (pin "1") (pinfunction "TX_1") (pintype "unspecified"))
    )
    (net (code "107") (name "Net-(U1-D1{slash}TX)") (class "Default")
      (node (ref "U1") (pin "1") (pinfunction "D1/TX_1") (pintype "unspecified"))
      (node (ref "U2") (pin "2") (pinfunction "RX_2") (pintype "unspecified"))
    )
    (net (code "108") (name "Net-(U1-D3)") (class "Default")
      (node (ref "U1") (pin "6") (pinfunction "D3_6") (pintype "unspecified"))
      (node (ref "U3") (pin "3") (pinfunction "OUT_3") (pintype "unspecified"))
    )
    (net (code "109") (name "Net-(U1-D7)") (class "Default")
      (node (ref "U1") (pin "10") (pinfunction "D7_10") (pintype "unspecified"))
      (node (ref "U3") (pin "8") (pinfunction "DIR_8") (pintype "unspecified"))
    )
    (net (code "110") (name "VCC") (class "Default")
      (node (ref "C1") (pin "2") (pinfunction "2_2") (pintype "unspecified"))
      (node (ref "C2") (pin "2") (pinfunction "2_2") (pintype "unspecified"))
      (node (ref "H1") (pin "1") (pinfunction "1_1") (pintype "input"))
      (node (ref "R1") (pin "2") (pinfunction "2_2") (pintype "unspecified"))
      (node (ref "R2") (pin "2") (pinfunction "2_2") (pintype "unspecified"))
      (node (ref "R3") (pin "2") (pinfunction "2_2") (pintype "unspecified"))
      (node (ref "SK1") (pin "4") (pinfunction "VCC_4") (pintype "unspecified"))
      (node (ref "SK11") (pin "4") (pinfunction "VCC_4") (pintype "unspecified"))
      (node (ref "SK12") (pin "4") (pinfunction "VCC_4") (pintype "unspecified"))
      (node (ref "SK13") (pin "4") (pinfunction "VCC_4") (pintype "unspecified"))
      (node (ref "SK14") (pin "4") (pinfunction "VCC_4") (pintype "unspecified"))
      (node (ref "SK15") (pin "4") (pinfunction "VCC_4") (pintype "unspecified"))
      (node (ref "SK16") (pin "4") (pinfunction "VCC_4") (pintype "unspecified"))
      (node (ref "SK17") (pin "4") (pinfunction "VCC_4") (pintype "unspecified"))
      (node (ref "SK18") (pin "4") (pinfunction "VCC_4") (pintype "unspecified"))
      (node (ref "SK19") (pin "4") (pinfunction "VCC_4") (pintype "unspecified"))
      (node (ref "SK20") (pin "4") (pinfunction "VCC_4") (pintype "unspecified"))
      (node (ref "SK21") (pin "4") (pinfunction "VCC_4") (pintype "unspecified"))
      (node (ref "SK22") (pin "4") (pinfunction "VCC_4") (pintype "unspecified"))
      (node (ref "SK23") (pin "4") (pinfunction "VCC_4") (pintype "unspecified"))
      (node (ref "SK24") (pin "4") (pinfunction "VCC_4") (pintype "unspecified"))
      (node (ref "SK25") (pin "4") (pinfunction "VCC_4") (pintype "unspecified"))
      (node (ref "SK26") (pin "4") (pinfunction "VCC_4") (pintype "unspecified"))
      (node (ref "SK27") (pin "4") (pinfunction "VCC_4") (pintype "unspecified"))
      (node (ref "SK28") (pin "4") (pinfunction "VCC_4") (pintype "unspecified"))
      (node (ref "SK29") (pin "4") (pinfunction "VCC_4") (pintype "unspecified"))
      (node (ref "SK30") (pin "4") (pinfunction "VCC_4") (pintype "unspecified"))
      (node (ref "SK31") (pin "4") (pinfunction "VCC_4") (pintype "unspecified"))
      (node (ref "SK32") (pin "4") (pinfunction "VCC_4") (pintype "unspecified"))
      (node (ref "SK33") (pin "4") (pinfunction "VCC_4") (pintype "unspecified"))
      (node (ref "SK34") (pin "4") (pinfunction "VCC_4") (pintype "unspecified"))
      (node (ref "SK35") (pin "4") (pinfunction "VCC_4") (pintype "unspecified"))
      (node (ref "SK36") (pin "4") (pinfunction "VCC_4") (pintype "unspecified"))
      (node (ref "SK37") (pin "4") (pinfunction "VCC_4") (pintype "unspecified"))
      (node (ref "SK38") (pin "4") (pinfunction "VCC_4") (pintype "unspecified"))
      (node (ref "SK39") (pin "4") (pinfunction "VCC_4") (pintype "unspecified"))
      (node (ref "SK40") (pin "4") (pinfunction "VCC_4") (pintype "unspecified"))
      (node (ref "SK41") (pin "4") (pinfunction "VCC_4") (pintype "unspecified"))
      (node (ref "SK42") (pin "4") (pinfunction "VCC_4") (pintype "unspecified"))
      (node (ref "SK43") (pin "4") (pinfunction "VCC_4") (pintype "unspecified"))
      (node (ref "SK44") (pin "4") (pinfunction "VCC_4") (pintype "unspecified"))
      (node (ref "SK45") (pin "4") (pinfunction "VCC_4") (pintype "unspecified"))
      (node (ref "SK46") (pin "4") (pinfunction "VCC_4") (pintype "unspecified"))
      (node (ref "SK47") (pin "4") (pinfunction "VCC_4") (pintype "unspecified"))
      (node (ref "SK48") (pin "4") (pinfunction "VCC_4") (pintype "unspecified"))
      (node (ref "SK49") (pin "4") (pinfunction "VCC_4") (pintype "unspecified"))
      (node (ref "SK50") (pin "4") (pinfunction "VCC_4") (pintype "unspecified"))
      (node (ref "SK51") (pin "4") (pinfunction "VCC_4") (pintype "unspecified"))
      (node (ref "SK52") (pin "4") (pinfunction "VCC_4") (pintype "unspecified"))
      (node (ref "SK53") (pin "4") (pinfunction "VCC_4") (pintype "unspecified"))
      (node (ref "SK54") (pin "4") (pinfunction "VCC_4") (pintype "unspecified"))
      (node (ref "SK55") (pin "4") (pinfunction "VCC_4") (pintype "unspecified"))
      (node (ref "SK56") (pin "4") (pinfunction "VCC_4") (pintype "unspecified"))
      (node (ref "SK57") (pin "4") (pinfunction "VCC_4") (pintype "unspecified"))
      (node (ref "SK58") (pin "4") (pinfunction "VCC_4") (pintype "unspecified"))
      (node (ref "SK59") (pin "4") (pinfunction "VCC_4") (pintype "unspecified"))
      (node (ref "U3") (pin "1") (pinfunction "VDD5V_1") (pintype "unspecified"))
    )
    (net (code "111") (name "unconnected-(SK1-CKO-Pad5)") (class "Default")
      (node (ref "SK1") (pin "5") (pinfunction "CKO_5") (pintype "unspecified"))
    )
    (net (code "112") (name "unconnected-(SK1-SDO-Pad6)") (class "Default")
      (node (ref "SK1") (pin "6") (pinfunction "SDO_6") (pintype "unspecified"))
    )
    (net (code "113") (name "unconnected-(U1-A0-Pad19)") (class "Default")
      (node (ref "U1") (pin "19") (pinfunction "A0_19") (pintype "unspecified"))
    )
    (net (code "114") (name "unconnected-(U1-A1-Pad20)") (class "Default")
      (node (ref "U1") (pin "20") (pinfunction "A1_20") (pintype "unspecified"))
    )
    (net (code "115") (name "unconnected-(U1-A2-Pad21)") (class "Default")
      (node (ref "U1") (pin "21") (pinfunction "A2_21") (pintype "unspecified"))
    )
    (net (code "116") (name "unconnected-(U1-A3-Pad22)") (class "Default")
      (node (ref "U1") (pin "22") (pinfunction "A3_22") (pintype "unspecified"))
    )
    (net (code "117") (name "unconnected-(U1-A6-Pad25)") (class "Default")
      (node (ref "U1") (pin "25") (pinfunction "A6_25") (pintype "unspecified"))
    )
    (net (code "118") (name "unconnected-(U1-A7-Pad26)") (class "Default")
      (node (ref "U1") (pin "26") (pinfunction "A7_26") (pintype "unspecified"))
    )
    (net (code "119") (name "unconnected-(U1-AREF-Pad18)") (class "Default")
      (node (ref "U1") (pin "18") (pinfunction "AREF_18") (pintype "unspecified"))
    )
    (net (code "120") (name "unconnected-(U1-D2-Pad5)") (class "Default")
      (node (ref "U1") (pin "5") (pinfunction "D2_5") (pintype "unspecified"))
    )
    (net (code "121") (name "unconnected-(U1-D4-Pad7)") (class "Default")
      (node (ref "U1") (pin "7") (pinfunction "D4_7") (pintype "unspecified"))
    )
    (net (code "122") (name "unconnected-(U1-D5-Pad8)") (class "Default")
      (node (ref "U1") (pin "8") (pinfunction "D5_8") (pintype "unspecified"))
    )
    (net (code "123") (name "unconnected-(U1-D6-Pad9)") (class "Default")
      (node (ref "U1") (pin "9") (pinfunction "D6_9") (pintype "unspecified"))
    )
    (net (code "124") (name "unconnected-(U1-D8-Pad11)") (class "Default")
      (node (ref "U1") (pin "11") (pinfunction "D8_11") (pintype "unspecified"))
    )
    (net (code "125") (name "unconnected-(U1-D9-Pad12)") (class "Default")
      (node (ref "U1") (pin "12") (pinfunction "D9_12") (pintype "unspecified"))
    )
    (net (code "126") (name "unconnected-(U1-D10-Pad13)") (class "Default")
      (node (ref "U1") (pin "13") (pinfunction "D10_13") (pintype "unspecified"))
    )
    (net (code "127") (name "unconnected-(U1-D12-Pad15)") (class "Default")
      (node (ref "U1") (pin "15") (pinfunction "D12_15") (pintype "unspecified"))
    )
    (net (code "128") (name "unconnected-(U1-RESET-Pad3)") (class "Default")
      (node (ref "U1") (pin "3") (pinfunction "RESET_3") (pintype "unspecified"))
    )
    (net (code "129") (name "unconnected-(U1-RESET-Pad28)") (class "Default")
      (node (ref "U1") (pin "28") (pinfunction "RESET_28") (pintype "unspecified"))
    )
    (net (code "130") (name "unconnected-(U1-VIN-Pad30)") (class "Default")
      (node (ref "U1") (pin "30") (pinfunction "VIN_30") (pintype "unspecified"))
    )
    (net (code "131") (name "unconnected-(U3-PGO-Pad5)") (class "Default")
      (node (ref "U3") (pin "5") (pinfunction "PGO_5") (pintype "unspecified"))
    )
    (net (code "132") (name "unconnected-(U3-VDD3V3-Pad2)") (class "Default")
      (node (ref "U3") (pin "2") (pinfunction "VDD3V3_2") (pintype "unspecified"))
    )
  )
)
